# ADC.net
KiCad netlist of a schematic drawn in Altium Designer
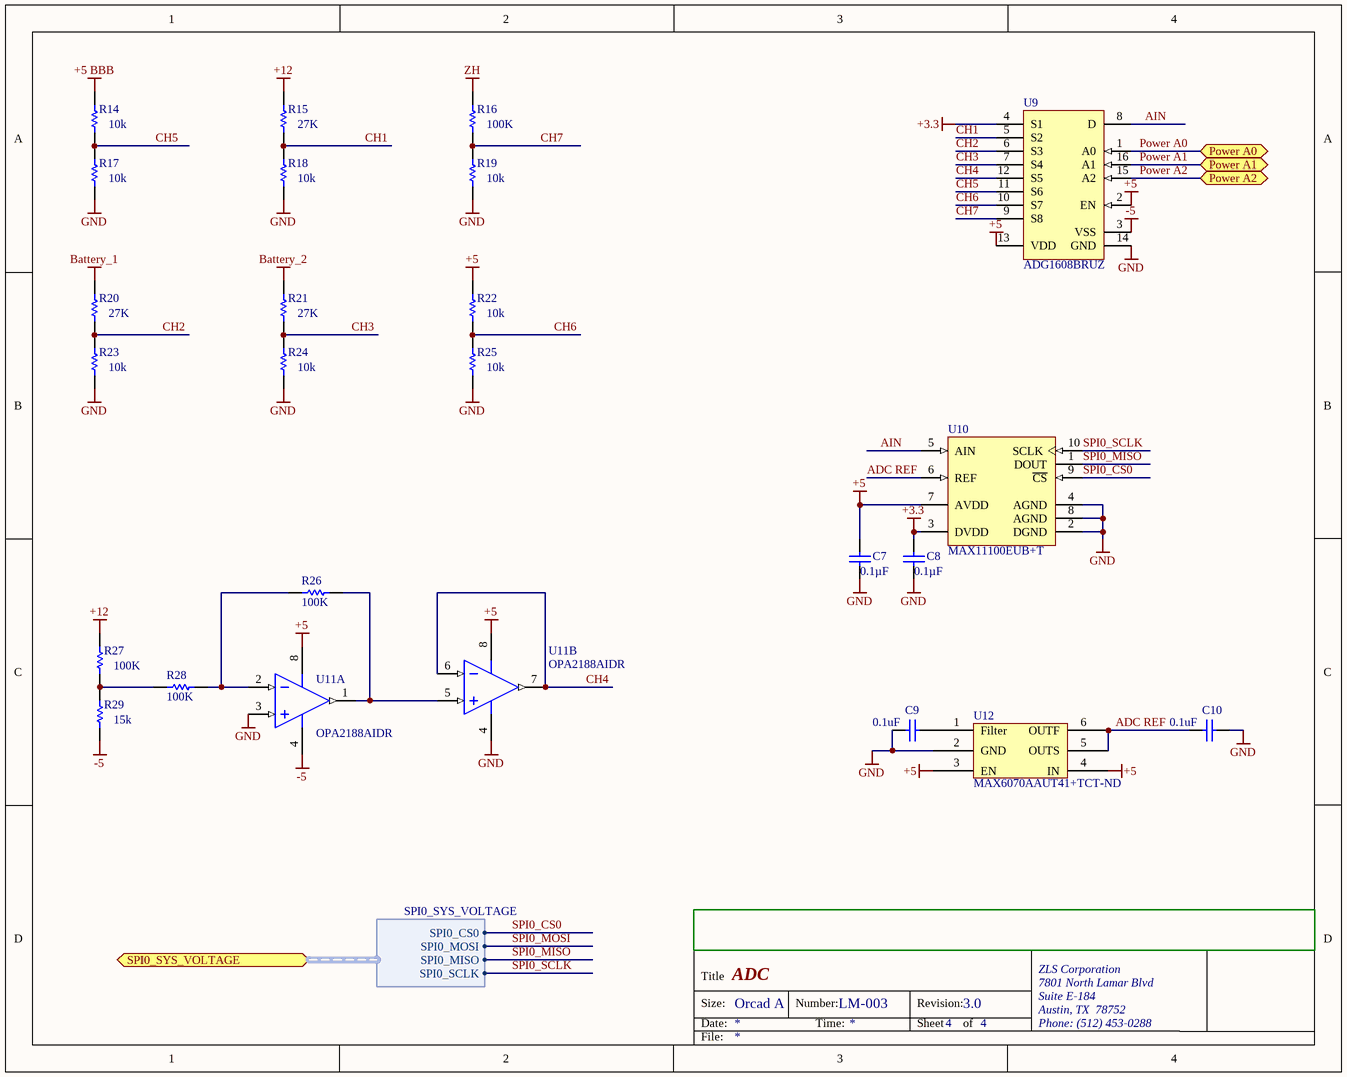
[diagram p0: ADC.SchDoc]

(export (version "E")
  (design (tool "Eeschema 10.0.6"))
  (components
    (comp (ref "C7")
      (value "CAP CER 0.1UF 25V X7R 0805")
      (footprint "CAPC0805(2012)145_N")
      (fields
        (field (name "MANUFACTURER") "Murata Electronics North America")
        (field (name "MANUFACTURER PART NUMBER") "GRM21BR71E104KA01L")
        (field (name "CAPACITANCE") "0.1µF")
        (field (name "TOLERANCE") "±10%")
      )
      (libsource (lib "Altium Content Vault") (part "CMP-1036-04795-1"))
    )
    (comp (ref "C8")
      (value "CAP CER 0.1UF 25V X7R 0805")
      (footprint "CAPC0805(2012)145_N")
      (fields
        (field (name "MANUFACTURER") "Murata Electronics North America")
        (field (name "MANUFACTURER PART NUMBER") "GRM21BR71E104KA01L")
        (field (name "CAPACITANCE") "0.1µF")
        (field (name "TOLERANCE") "±10%")
      )
      (libsource (lib "Altium Content Vault") (part "CMP-1036-04795-1"))
    )
    (comp (ref "C9")
      (value "0.1uF")
      (footprint "CAPC0402(1005)60_L")
      (description "CAP CER 0.1UF 10V X7R 0402")
      (fields
        (field (name "MANUFACTURER") "Murata Electronics North America")
        (field (name "MANUFACTURER PART NUMBER") "GRM155R71A104KA01D")
      )
      (libsource (lib "Altium Content Vault") (part "CMP-1034-00252-1"))
    )
    (comp (ref "C10")
      (value "0.1uF")
      (footprint "CAPC0402(1005)60_L")
      (description "CAP CER 0.1UF 10V X7R 0402")
      (fields
        (field (name "MANUFACTURER") "Murata Electronics North America")
        (field (name "MANUFACTURER PART NUMBER") "GRM155R71A104KA01D")
      )
      (libsource (lib "Altium Content Vault") (part "CMP-1034-00252-1"))
    )
    (comp (ref "R14")
      (value "10k")
      (footprint "RESC0402(1005)_L")
      (description "RES SMD 10K OHM 1% 1/10W 0402")
      (fields
        (field (name "MANUFACTURER") "Vishay Beyschlag")
        (field (name "MANUFACTURER PART NUMBER") "MCS0402MC1002FE000")
      )
      (libsource (lib "Altium Content Vault") (part "CMP-1011-00927-1"))
    )
    (comp (ref "R15")
      (value "27K")
      (footprint "RESC0402(1005)_L")
      (description "RES SMD 27K OHM 1% 1/10W 0402")
      (fields
        (field (name "MANUFACTURER") "Vishay Beyschlag")
        (field (name "MANUFACTURER PART NUMBER") "MCS04020C2702FE000")
      )
      (libsource (lib "Altium Content Vault") (part "CMP-1011-00927-1"))
    )
    (comp (ref "R16")
      (value "100K")
      (footprint "RESC0402(1005)_L")
      (description "RES SMD 100K OHM 1% 1/10W 0402")
      (fields
        (field (name "MANUFACTURER") "Vishay Beyschlag")
        (field (name "MANUFACTURER PART NUMBER") "MCS04020C1003FE000")
      )
      (libsource (lib "Altium Content Vault") (part "CMP-1011-00927-1"))
    )
    (comp (ref "R17")
      (value "10k")
      (footprint "RESC0402(1005)_L")
      (description "RES SMD 10K OHM 1% 1/10W 0402")
      (fields
        (field (name "MANUFACTURER") "Vishay Beyschlag")
        (field (name "MANUFACTURER PART NUMBER") "MCS0402MC1002FE000")
      )
      (libsource (lib "Altium Content Vault") (part "CMP-1011-00927-1"))
    )
    (comp (ref "R18")
      (value "10k")
      (footprint "RESC0402(1005)_L")
      (description "RES SMD 10K OHM 1% 1/10W 0402")
      (fields
        (field (name "MANUFACTURER") "Vishay Beyschlag")
        (field (name "MANUFACTURER PART NUMBER") "MCS0402MC1002FE000")
      )
      (libsource (lib "Altium Content Vault") (part "CMP-1011-00927-1"))
    )
    (comp (ref "R19")
      (value "10k")
      (footprint "RESC0402(1005)_L")
      (description "RES SMD 10K OHM 1% 1/10W 0402")
      (fields
        (field (name "MANUFACTURER") "Vishay Beyschlag")
        (field (name "MANUFACTURER PART NUMBER") "MCS0402MC1002FE000")
      )
      (libsource (lib "Altium Content Vault") (part "CMP-1011-00927-1"))
    )
    (comp (ref "R20")
      (value "27K")
      (footprint "RESC0402(1005)_L")
      (description "RES SMD 27K OHM 1% 1/10W 0402")
      (fields
        (field (name "MANUFACTURER") "Vishay Beyschlag")
        (field (name "MANUFACTURER PART NUMBER") "MCS04020C2702FE000")
      )
      (libsource (lib "Altium Content Vault") (part "CMP-1011-00927-1"))
    )
    (comp (ref "R21")
      (value "27K")
      (footprint "RESC0402(1005)_L")
      (description "RES SMD 27K OHM 1% 1/10W 0402")
      (fields
        (field (name "MANUFACTURER") "Vishay Beyschlag")
        (field (name "MANUFACTURER PART NUMBER") "MCS04020C2702FE000")
      )
      (libsource (lib "Altium Content Vault") (part "CMP-1011-00927-1"))
    )
    (comp (ref "R22")
      (value "10k")
      (footprint "RESC0402(1005)_L")
      (description "RES SMD 10K OHM 1% 1/10W 0402")
      (fields
        (field (name "MANUFACTURER") "Vishay Beyschlag")
        (field (name "MANUFACTURER PART NUMBER") "MCS0402MC1002FE000")
      )
      (libsource (lib "Altium Content Vault") (part "CMP-1011-00927-1"))
    )
    (comp (ref "R23")
      (value "10k")
      (footprint "RESC0402(1005)_L")
      (description "RES SMD 10K OHM 1% 1/10W 0402")
      (fields
        (field (name "MANUFACTURER") "Vishay Beyschlag")
        (field (name "MANUFACTURER PART NUMBER") "MCS0402MC1002FE000")
      )
      (libsource (lib "Altium Content Vault") (part "CMP-1011-00927-1"))
    )
    (comp (ref "R24")
      (value "10k")
      (footprint "RESC0402(1005)_L")
      (description "RES SMD 10K OHM 1% 1/10W 0402")
      (fields
        (field (name "MANUFACTURER") "Vishay Beyschlag")
        (field (name "MANUFACTURER PART NUMBER") "MCS0402MC1002FE000")
      )
      (libsource (lib "Altium Content Vault") (part "CMP-1011-00927-1"))
    )
    (comp (ref "R25")
      (value "10k")
      (footprint "RESC0402(1005)_L")
      (description "RES SMD 10K OHM 1% 1/10W 0402")
      (fields
        (field (name "MANUFACTURER") "Vishay Beyschlag")
        (field (name "MANUFACTURER PART NUMBER") "MCS0402MC1002FE000")
      )
      (libsource (lib "Altium Content Vault") (part "CMP-1011-00927-1"))
    )
    (comp (ref "R26")
      (value "100K")
      (footprint "RESC0402(1005)_L")
      (description "RES SMD 100K OHM 1% 1/10W 0402")
      (fields
        (field (name "MANUFACTURER") "Vishay Beyschlag")
        (field (name "MANUFACTURER PART NUMBER") "MCS04020C1003FE000")
      )
      (libsource (lib "Altium Content Vault") (part "CMP-1011-00927-1"))
    )
    (comp (ref "R27")
      (value "100K")
      (footprint "RESC0402(1005)_L")
      (description "RES SMD 100K OHM 1% 1/10W 0402")
      (fields
        (field (name "MANUFACTURER") "Vishay Beyschlag")
        (field (name "MANUFACTURER PART NUMBER") "MCS04020C1003FE000")
      )
      (libsource (lib "Altium Content Vault") (part "CMP-1011-00927-1"))
    )
    (comp (ref "R28")
      (value "100K")
      (footprint "RESC0402(1005)_L")
      (description "RES SMD 100K OHM 1% 1/10W 0402")
      (fields
        (field (name "MANUFACTURER") "Vishay Beyschlag")
        (field (name "MANUFACTURER PART NUMBER") "MCS04020C1003FE000")
      )
      (libsource (lib "Altium Content Vault") (part "CMP-1011-00927-1"))
    )
    (comp (ref "R29")
      (value "15k")
      (footprint "RESC0402(1005)_L")
      (description "RES SMD 15K OHM 1% 1/10W 0402")
      (fields
        (field (name "MANUFACTURER") "Vishay Beyschlag")
        (field (name "MANUFACTURER PART NUMBER") "MCS04020C1502FE000")
      )
      (libsource (lib "Altium Content Vault") (part "CMP-1011-00927-1"))
    )
    (comp (ref "U9")
      (value "ADG1608BRUZ")
      (footprint "ADI-RU-16_M")
      (description "IC MULTIPLEXER 8X1 16TSSOP")
      (fields (field (name "MANUFACTURER") "Analog Devices Inc."))
      (libsource (lib "Altium Content Vault") (part "CMP-0793-00136-1"))
    )
    (comp (ref "U10")
      (value "MAX11100EUB+T")
      (footprint "U10+2_L")
      (description "IC ADC 16BIT SRL 200KSPS 10UMAX")
      (fields
        (field (name "MANUFACTURER") "Maxim Integrated")
        (field (name "MANUFACTURER PART NUMBER") "MAX11100EUB+")
      )
      (libsource (lib "Altium Content Vault") (part "CMP-0249-00017-1"))
    )
    (comp (ref "U11")
      (value "OPA2188AIDR")
      (footprint "D0008A_L")
      (description "IC OPAMP ZERO-DRIFT 2MHZ 8SOIC")
      (fields (field (name "MANUFACTURER") "Texas Instruments") (field (name "BASE PART NUMBER") "OPA2188"))
      (libsource (lib "Altium Content Vault") (part "CMP-0272-00241-3"))
    )
    (comp (ref "U12")
      (value "MAX6070AAUT41+T")
      (footprint "SOT95P280X445-6N")
      (description "IC VREF SERIES 4.096V SOT23")
      (fields
        (field (name "SUPPLIER PART NUMBER 1") "MAX6070AAUT41+TCT-ND")
        (field (name "MANUFACTURER") "Maxim Integrated")
        (field (name "TOLERANCE") "±0.04%")
      )
      (libsource (lib "ZLS_Schematic_lib") (part "MAX6070AAUT41+T"))
    )
  )
  (nets
    (net (code "2") (name "+3.3") (class "Default")
      (node (ref "C8") (pin "1") (pinfunction "1_1") (pintype "passive"))
      (node (ref "U10") (pin "3") (pinfunction "DVDD_3") (pintype "power_in"))
      (node (ref "U9") (pin "4") (pinfunction "S1_4") (pintype "passive"))
    )
    (net (code "3") (name "+5") (class "Default")
      (node (ref "C7") (pin "1") (pinfunction "1_1") (pintype "passive"))
      (node (ref "R22") (pin "2") (pinfunction "2_2") (pintype "passive"))
      (node (ref "U10") (pin "7") (pinfunction "AVDD_7") (pintype "power_in"))
      (node (ref "U11") (pin "8") (pinfunction "V+_8") (pintype "power_in"))
      (node (ref "U12") (pin "3") (pinfunction "EN_3") (pintype "passive"))
      (node (ref "U12") (pin "4") (pinfunction "IN_4") (pintype "passive"))
      (node (ref "U9") (pin "13") (pinfunction "VDD_13") (pintype "power_in"))
      (node (ref "U9") (pin "2") (pinfunction "EN_2") (pintype "input"))
    )
    (net (code "4") (name "+5 BBB") (class "Default")
      (node (ref "R14") (pin "2") (pinfunction "2_2") (pintype "passive"))
    )
    (net (code "5") (name "+12") (class "Default")
      (node (ref "R15") (pin "2") (pinfunction "2_2") (pintype "passive"))
      (node (ref "R27") (pin "2") (pinfunction "2_2") (pintype "passive"))
    )
    (net (code "6") (name "-5") (class "Default")
      (node (ref "R29") (pin "1") (pinfunction "1_1") (pintype "passive"))
      (node (ref "U11") (pin "4") (pinfunction "V-_4") (pintype "power_in"))
      (node (ref "U9") (pin "3") (pinfunction "VSS_3") (pintype "power_in"))
    )
    (net (code "7") (name "/ADC REF") (class "Default")
      (node (ref "C10") (pin "2") (pinfunction "2_2") (pintype "passive"))
      (node (ref "U10") (pin "6") (pinfunction "REF_6") (pintype "input"))
      (node (ref "U12") (pin "5") (pinfunction "OUTS_5") (pintype "passive"))
      (node (ref "U12") (pin "6") (pinfunction "OUTF_6") (pintype "passive"))
    )
    (net (code "8") (name "/AIN") (class "Default")
      (node (ref "U10") (pin "5") (pinfunction "AIN_5") (pintype "input"))
      (node (ref "U9") (pin "8") (pinfunction "D_8") (pintype "passive"))
    )
    (net (code "9") (name "/CH1") (class "Default")
      (node (ref "R15") (pin "1") (pinfunction "1_1") (pintype "passive"))
      (node (ref "R18") (pin "2") (pinfunction "2_2") (pintype "passive"))
      (node (ref "U9") (pin "5") (pinfunction "S2_5") (pintype "passive"))
    )
    (net (code "10") (name "/CH2") (class "Default")
      (node (ref "R20") (pin "1") (pinfunction "1_1") (pintype "passive"))
      (node (ref "R23") (pin "2") (pinfunction "2_2") (pintype "passive"))
      (node (ref "U9") (pin "6") (pinfunction "S3_6") (pintype "passive"))
    )
    (net (code "11") (name "/CH3") (class "Default")
      (node (ref "R21") (pin "1") (pinfunction "1_1") (pintype "passive"))
      (node (ref "R24") (pin "2") (pinfunction "2_2") (pintype "passive"))
      (node (ref "U9") (pin "7") (pinfunction "S4_7") (pintype "passive"))
    )
    (net (code "12") (name "/CH4") (class "Default")
      (node (ref "U11") (pin "6") (pinfunction "IN_B-_6") (pintype "input"))
      (node (ref "U11") (pin "7") (pinfunction "OUT_B_7") (pintype "output"))
      (node (ref "U9") (pin "12") (pinfunction "S5_12") (pintype "passive"))
    )
    (net (code "13") (name "/CH5") (class "Default")
      (node (ref "R14") (pin "1") (pinfunction "1_1") (pintype "passive"))
      (node (ref "R17") (pin "2") (pinfunction "2_2") (pintype "passive"))
      (node (ref "U9") (pin "11") (pinfunction "S6_11") (pintype "passive"))
    )
    (net (code "14") (name "/CH6") (class "Default")
      (node (ref "R22") (pin "1") (pinfunction "1_1") (pintype "passive"))
      (node (ref "R25") (pin "2") (pinfunction "2_2") (pintype "passive"))
      (node (ref "U9") (pin "10") (pinfunction "S7_10") (pintype "passive"))
    )
    (net (code "15") (name "/CH7") (class "Default")
      (node (ref "R16") (pin "1") (pinfunction "1_1") (pintype "passive"))
      (node (ref "R19") (pin "2") (pinfunction "2_2") (pintype "passive"))
      (node (ref "U9") (pin "9") (pinfunction "S8_9") (pintype "passive"))
    )
    (net (code "16") (name "/Power A0") (class "Default")
      (node (ref "U9") (pin "1") (pinfunction "A0_1") (pintype "input"))
    )
    (net (code "17") (name "/Power A1") (class "Default")
      (node (ref "U9") (pin "16") (pinfunction "A1_16") (pintype "input"))
    )
    (net (code "18") (name "/Power A2") (class "Default")
      (node (ref "U9") (pin "15") (pinfunction "A2_15") (pintype "input"))
    )
    (net (code "19") (name "/SPI0_CS0") (class "Default")
      (node (ref "U10") (pin "9") (pinfunction "~{CS}_9") (pintype "input"))
    )
    (net (code "20") (name "/SPI0_MISO") (class "Default")
      (node (ref "U10") (pin "1") (pinfunction "DOUT_1") (pintype "tri_state"))
    )
    (net (code "22") (name "/SPI0_SCLK") (class "Default")
      (node (ref "U10") (pin "10") (pinfunction "SCLK_10") (pintype "input"))
    )
    (net (code "24") (name "Battery_1") (class "Default")
      (node (ref "R20") (pin "2") (pinfunction "2_2") (pintype "passive"))
    )
    (net (code "25") (name "Battery_2") (class "Default")
      (node (ref "R21") (pin "2") (pinfunction "2_2") (pintype "passive"))
    )
    (net (code "26") (name "GND") (class "Default")
      (node (ref "C10") (pin "1") (pinfunction "1_1") (pintype "passive"))
      (node (ref "C7") (pin "2") (pinfunction "2_2") (pintype "passive"))
      (node (ref "C8") (pin "2") (pinfunction "2_2") (pintype "passive"))
      (node (ref "C9") (pin "2") (pinfunction "2_2") (pintype "passive"))
      (node (ref "R17") (pin "1") (pinfunction "1_1") (pintype "passive"))
      (node (ref "R18") (pin "1") (pinfunction "1_1") (pintype "passive"))
      (node (ref "R19") (pin "1") (pinfunction "1_1") (pintype "passive"))
      (node (ref "R23") (pin "1") (pinfunction "1_1") (pintype "passive"))
      (node (ref "R24") (pin "1") (pinfunction "1_1") (pintype "passive"))
      (node (ref "R25") (pin "1") (pinfunction "1_1") (pintype "passive"))
      (node (ref "U10") (pin "2") (pinfunction "DGND_2") (pintype "power_in"))
      (node (ref "U10") (pin "4") (pinfunction "AGND_4") (pintype "power_in"))
      (node (ref "U10") (pin "8") (pinfunction "AGND_8") (pintype "power_in"))
      (node (ref "U11") (pin "3") (pinfunction "IN_A+_3") (pintype "input"))
      (node (ref "U11") (pin "4") (pinfunction "V-_4") (pintype "power_in"))
      (node (ref "U12") (pin "2") (pinfunction "GND_2") (pintype "passive"))
      (node (ref "U9") (pin "14") (pinfunction "GND_14") (pintype "power_in"))
    )
    (net (code "27") (name "Net-(R27-Pad1)") (class "Default")
      (node (ref "R27") (pin "1") (pinfunction "1_1") (pintype "passive"))
      (node (ref "R28") (pin "2") (pinfunction "2_2") (pintype "passive"))
      (node (ref "R29") (pin "2") (pinfunction "2_2") (pintype "passive"))
    )
    (net (code "28") (name "Net-(U11A-IN_A-)") (class "Default")
      (node (ref "R26") (pin "2") (pinfunction "2_2") (pintype "passive"))
      (node (ref "R28") (pin "1") (pinfunction "1_1") (pintype "passive"))
      (node (ref "U11") (pin "2") (pinfunction "IN_A-_2") (pintype "input"))
    )
    (net (code "29") (name "Net-(U11A-OUT_A)") (class "Default")
      (node (ref "R26") (pin "1") (pinfunction "1_1") (pintype "passive"))
      (node (ref "U11") (pin "1") (pinfunction "OUT_A_1") (pintype "output"))
      (node (ref "U11") (pin "5") (pinfunction "IN_B+_5") (pintype "input"))
    )
    (net (code "30") (name "Net-(U12-Filter)") (class "Default")
      (node (ref "C9") (pin "1") (pinfunction "1_1") (pintype "passive"))
      (node (ref "U12") (pin "1") (pinfunction "Filter_1") (pintype "passive"))
    )
    (net (code "31") (name "ZH") (class "Default")
      (node (ref "R16") (pin "2") (pinfunction "2_2") (pintype "passive"))
    )
  )
)
